# PowerSupplyFromArduino.net
KiCad netlist of a schematic drawn in EAGLE
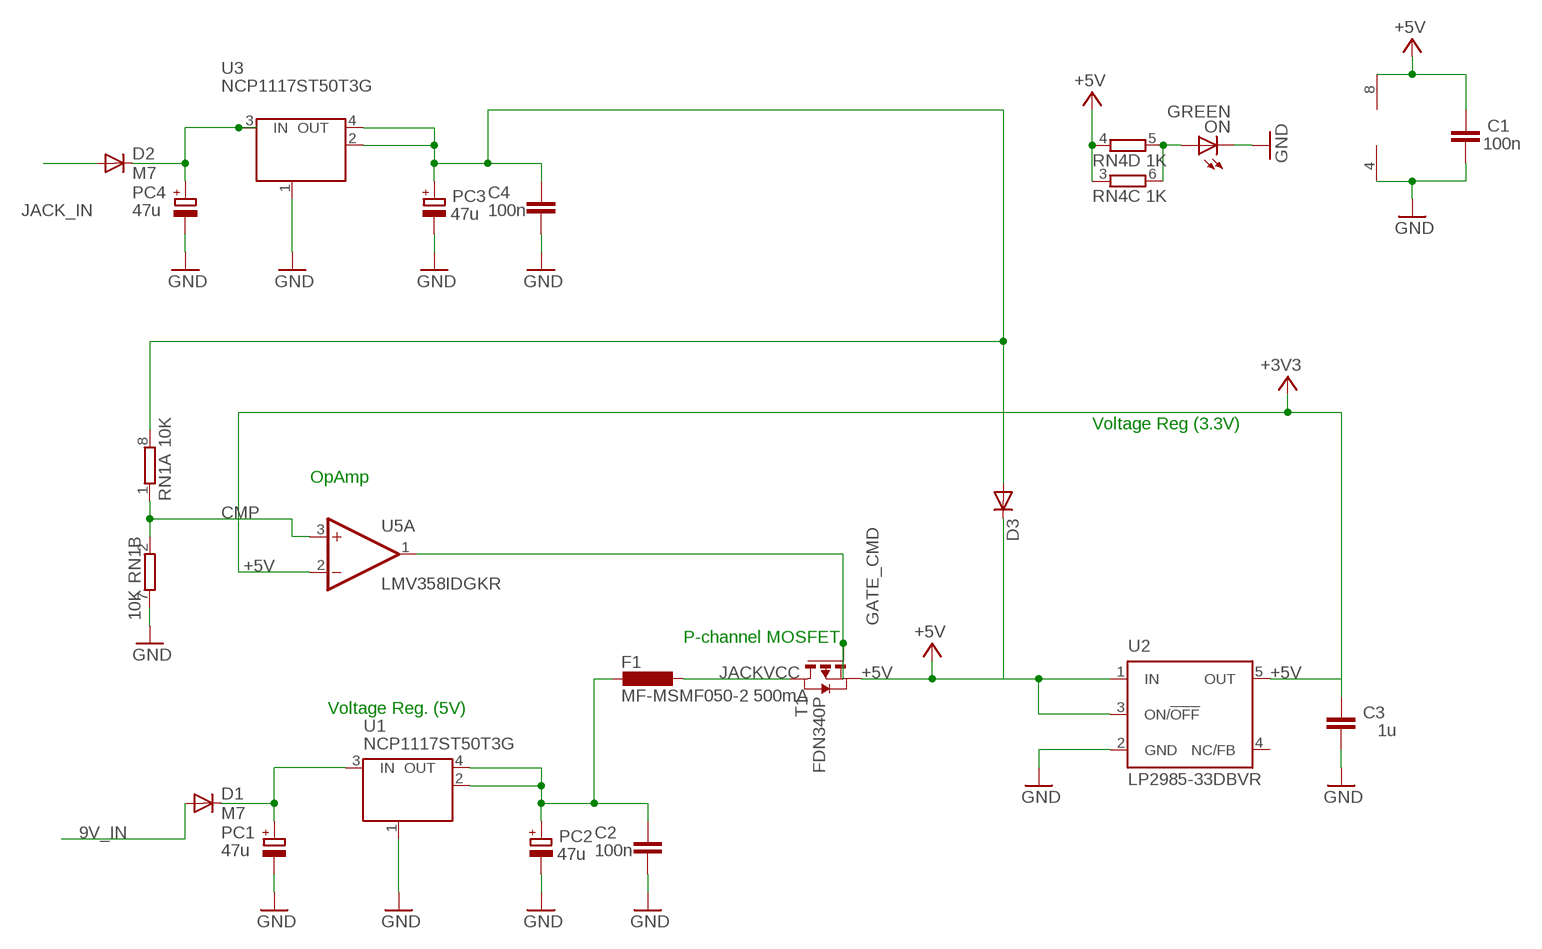
[diagram p0: schematic, sheet 1]

(export (version "E")
  (design (tool "Eeschema 10.0.6"))
  (components
    (comp (ref "C1")
      (value "100n")
      (footprint "eagle-import:C0603-ROUND")
      (libsource (lib "eagle-import") (part "C-EU0603-RND"))
    )
    (comp (ref "C2")
      (value "100n")
      (footprint "eagle-import:C0603-ROUND")
      (libsource (lib "eagle-import") (part "C-EU0603-RND"))
    )
    (comp (ref "C3")
      (value "1u")
      (footprint "eagle-import:C0603-ROUND")
      (libsource (lib "eagle-import") (part "C-EU0603-RND"))
    )
    (comp (ref "C4")
      (value "100n")
      (footprint "eagle-import:C0603-ROUND")
      (libsource (lib "eagle-import") (part "C-EU0603-RND"))
    )
    (comp (ref "D1")
      (value "M7")
      (footprint "eagle-import:SMB")
      (libsource (lib "eagle-import") (part "DIODE-SMB"))
    )
    (comp (ref "D2")
      (value "M7")
      (footprint "eagle-import:SMB")
      (libsource (lib "eagle-import") (part "DIODE-SMB"))
    )
    (comp (ref "D3")
      (value "1N4004")
      (footprint "eagle-import:DO41-10")
      (libsource (lib "eagle-import") (part "1N4004"))
    )
    (comp (ref "F1")
      (value "MF-MSMF050-2 500mA")
      (footprint "eagle-import:L1812")
      (libsource (lib "eagle-import") (part "L-EUL1812"))
    )
    (comp (ref "ON")
      (value "GREEN")
      (footprint "eagle-import:CHIP-LED0805")
      (libsource (lib "eagle-import") (part "LEDCHIP-LED0805"))
    )
    (comp (ref "PC1")
      (value "47u")
      (footprint "eagle-import:PANASONIC_D")
      (libsource (lib "eagle-import") (part "CPOL-EUD"))
    )
    (comp (ref "PC2")
      (value "47u")
      (footprint "eagle-import:PANASONIC_D")
      (libsource (lib "eagle-import") (part "CPOL-EUD"))
    )
    (comp (ref "PC3")
      (value "47u")
      (footprint "eagle-import:PANASONIC_D")
      (libsource (lib "eagle-import") (part "CPOL-EUD"))
    )
    (comp (ref "PC4")
      (value "47u")
      (footprint "eagle-import:PANASONIC_D")
      (libsource (lib "eagle-import") (part "CPOL-EUD"))
    )
    (comp (ref "RN1")
      (value "10K")
      (footprint "eagle-import:CAY16")
      (libsource (lib "eagle-import") (part "4R-NCAY16"))
    )
    (comp (ref "RN4")
      (value "1K")
      (footprint "eagle-import:CAY16")
      (libsource (lib "eagle-import") (part "4R-NCAY16"))
    )
    (comp (ref "T1")
      (value "FDN340P")
      (footprint "eagle-import:SOT-23")
      (libsource (lib "eagle-import") (part "PMOSSOT23"))
    )
    (comp (ref "U1")
      (value "NCP1117ST50T3G")
      (footprint "eagle-import:SOT223")
      (libsource (lib "eagle-import") (part "MC33269ST-3.3T3"))
    )
    (comp (ref "U2")
      (value "LP2985-33DBVR")
      (footprint "eagle-import:SOT23-DBV")
      (libsource (lib "eagle-import") (part "LP2985-XXDBVR33"))
    )
    (comp (ref "U3")
      (value "NCP1117ST50T3G")
      (footprint "eagle-import:SOT223")
      (libsource (lib "eagle-import") (part "MC33269ST-3.3T3"))
    )
    (comp (ref "U5")
      (value "LMV358IDGKR")
      (footprint "eagle-import:MSOP08")
      (libsource (lib "eagle-import") (part "LMV358?MMX"))
    )
  )
  (nets
    (net (code "1") (name "+3V3") (class "Default")
      (node (ref "C1") (pin "2") (pinfunction "2_2") (pintype "passive"))
      (node (ref "C3") (pin "2") (pinfunction "2_2") (pintype "passive"))
      (node (ref "D3") (pin "C") (pinfunction "C_C") (pintype "passive"))
      (node (ref "RN4") (pin "3") (pinfunction "1_3") (pintype "passive"))
      (node (ref "RN4") (pin "4") (pinfunction "1_4") (pintype "passive"))
      (node (ref "T1") (pin "2") (pinfunction "S_2") (pintype "passive"))
      (node (ref "U2") (pin "1") (pinfunction "IN_1") (pintype "input"))
      (node (ref "U2") (pin "3") (pinfunction "ON/~{OFF}_3") (pintype "input"))
      (node (ref "U2") (pin "5") (pinfunction "OUT_5") (pintype "passive"))
      (node (ref "U5") (pin "2") (pinfunction "-IN_2") (pintype "input"))
      (node (ref "U5") (pin "8") (pinfunction "V+_8") (pintype "power_in"))
    )
    (net (code "2") (name "/9V_IN") (class "Default")
      (node (ref "D1") (pin "A") (pinfunction "A_A") (pintype "passive"))
    )
    (net (code "3") (name "/CMP") (class "Default")
      (node (ref "RN1") (pin "1") (pinfunction "1_1") (pintype "passive"))
      (node (ref "RN1") (pin "2") (pinfunction "1_2") (pintype "passive"))
      (node (ref "U5") (pin "3") (pinfunction "+IN_3") (pintype "input"))
    )
    (net (code "4") (name "/GATE_CMD") (class "Default")
      (node (ref "T1") (pin "3") (pinfunction "G_3") (pintype "passive"))
      (node (ref "U5") (pin "1") (pinfunction "OUT_1") (pintype "output"))
    )
    (net (code "5") (name "/JACKVCC") (class "Default")
      (node (ref "C2") (pin "2") (pinfunction "2_2") (pintype "passive"))
      (node (ref "F1") (pin "1") (pinfunction "1_1") (pintype "passive"))
      (node (ref "F1") (pin "2") (pinfunction "2_2") (pintype "passive"))
      (node (ref "PC2") (pin "+") (pinfunction "+_+") (pintype "passive"))
      (node (ref "T1") (pin "1") (pinfunction "D_1") (pintype "passive"))
      (node (ref "U1") (pin "2") (pinfunction "OUT_2") (pintype "passive"))
      (node (ref "U1") (pin "4") (pinfunction "OUT_4") (pintype "passive"))
    )
    (net (code "6") (name "/JACK_IN") (class "Default")
      (node (ref "D2") (pin "A") (pinfunction "A_A") (pintype "passive"))
    )
    (net (code "7") (name "GND") (class "Default")
      (node (ref "C1") (pin "1") (pinfunction "1_1") (pintype "passive"))
      (node (ref "C2") (pin "1") (pinfunction "1_1") (pintype "passive"))
      (node (ref "C3") (pin "1") (pinfunction "1_1") (pintype "passive"))
      (node (ref "C4") (pin "1") (pinfunction "1_1") (pintype "passive"))
      (node (ref "ON") (pin "C") (pinfunction "C_C") (pintype "passive"))
      (node (ref "PC1") (pin "-") (pinfunction "-_-") (pintype "passive"))
      (node (ref "PC2") (pin "-") (pinfunction "-_-") (pintype "passive"))
      (node (ref "PC3") (pin "-") (pinfunction "-_-") (pintype "passive"))
      (node (ref "PC4") (pin "-") (pinfunction "-_-") (pintype "passive"))
      (node (ref "RN1") (pin "7") (pinfunction "2_7") (pintype "passive"))
      (node (ref "U1") (pin "1") (pinfunction "GND/ADJ_1") (pintype "input"))
      (node (ref "U2") (pin "2") (pinfunction "GND_2") (pintype "power_in"))
      (node (ref "U3") (pin "1") (pinfunction "GND/ADJ_1") (pintype "input"))
      (node (ref "U5") (pin "4") (pinfunction "V-_4") (pintype "power_in"))
    )
    (net (code "8") (name "Net-(RN1A-2)") (class "Default")
      (node (ref "C4") (pin "2") (pinfunction "2_2") (pintype "passive"))
      (node (ref "D3") (pin "A") (pinfunction "A_A") (pintype "passive"))
      (node (ref "PC3") (pin "+") (pinfunction "+_+") (pintype "passive"))
      (node (ref "RN1") (pin "8") (pinfunction "2_8") (pintype "passive"))
      (node (ref "U3") (pin "2") (pinfunction "OUT_2") (pintype "passive"))
      (node (ref "U3") (pin "4") (pinfunction "OUT_4") (pintype "passive"))
    )
    (net (code "9") (name "Net-(RN4C-2)") (class "Default")
      (node (ref "ON") (pin "A") (pinfunction "A_A") (pintype "passive"))
      (node (ref "RN4") (pin "5") (pinfunction "2_5") (pintype "passive"))
      (node (ref "RN4") (pin "6") (pinfunction "2_6") (pintype "passive"))
    )
    (net (code "10") (name "Net-(U1-IN)") (class "Default")
      (node (ref "D1") (pin "C") (pinfunction "C_C") (pintype "passive"))
      (node (ref "PC1") (pin "+") (pinfunction "+_+") (pintype "passive"))
      (node (ref "U1") (pin "3") (pinfunction "IN_3") (pintype "input"))
    )
    (net (code "11") (name "Net-(U3-IN)") (class "Default")
      (node (ref "D2") (pin "C") (pinfunction "C_C") (pintype "passive"))
      (node (ref "PC4") (pin "+") (pinfunction "+_+") (pintype "passive"))
      (node (ref "U3") (pin "3") (pinfunction "IN_3") (pintype "input"))
    )
    (net (code "12") (name "unconnected-(U2-NC{slash}FB-Pad4)") (class "Default")
      (node (ref "U2") (pin "4") (pinfunction "NC/FB_4") (pintype "passive"))
    )
  )
)
